# SAM_E54_Xplained_Pro_CAN.net
KiCad netlist of a schematic drawn in Altium Designer
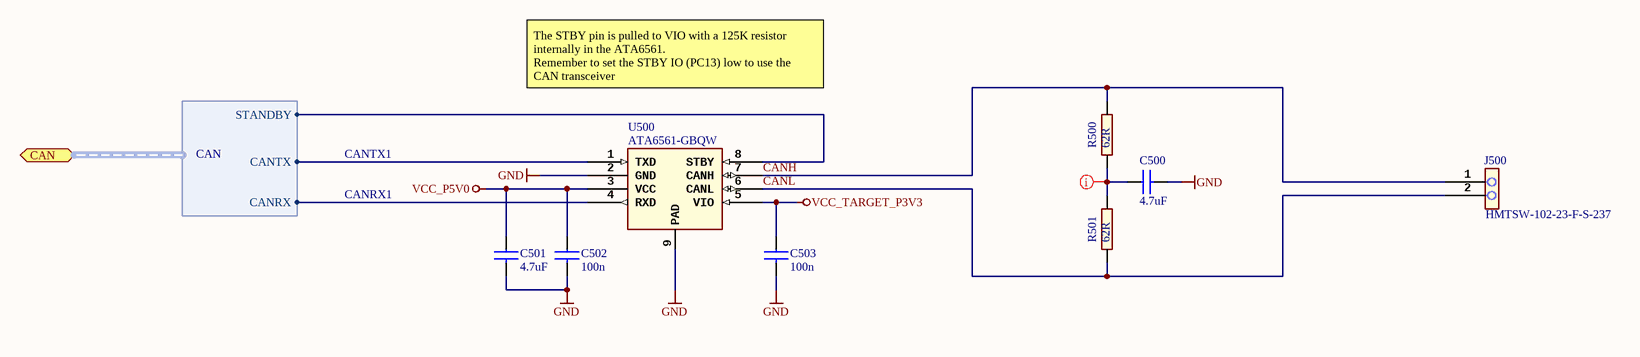
[diagram p0: SAM_E54_Xplained_Pro_CAN.SchDoc]

(export (version "E")
  (design (tool "Eeschema 10.0.6"))
  (components
    (comp (ref "C500")
      (value "4.7uF")
      (footprint "AP1-00003")
      (description "Ceramic capacitor, SMD 0805, X5R, 25V, Â±10 %")
      (fields (field (name "TOLERANCE") "Â±10%") (field (name "MANUFACTURER") "Murata"))
      (libsource (lib "AltiumDbLib") (part "CAP-NONPOL"))
    )
    (comp (ref "C501")
      (value "4.7uF")
      (footprint "AP1-00117")
      (description "Ceramic capacitor, SMD 0603, X5R, 10V, 10% (de31036)")
      (fields (field (name "TOLERANCE") "10%") (field (name "MANUFACTURER") "WALSIN Technology Corporation"))
      (libsource (lib "AltiumDbLib") (part "CAP-NONPOL"))
    )
    (comp (ref "C502")
      (value "100n")
      (footprint "AP1-00001")
      (description "Ceramic capacitor, SMD 0402, X7R, 16V, +/-10%")
      (fields (field (name "TOLERANCE") "16V, +/-10%") (field (name "MANUFACTURER") "Kemet"))
      (libsource (lib "AltiumDbLib") (part "CAP-NONPOL"))
    )
    (comp (ref "C503")
      (value "100n")
      (footprint "AP1-00001")
      (description "Ceramic capacitor, SMD 0402, X7R, 16V, +/-10%")
      (fields (field (name "TOLERANCE") "16V, +/-10%") (field (name "MANUFACTURER") "Kemet"))
      (libsource (lib "AltiumDbLib") (part "CAP-NONPOL"))
    )
    (comp (ref "J500")
      (value "HMTSW-102-23-F-S-237")
      (footprint "AP8-00733")
      (description "1x2 pin header, 2.54mm pitch, Pin-in-Paste THM")
      (fields (field (name "MANUFACTURER") "SAMTEC"))
      (libsource (lib "AltiumDbLib") (part "HEADER 1x2"))
    )
    (comp (ref "R500")
      (value "62R")
      (footprint "AP2-00008")
      (description "Thick film resistor, SMD 1210, 0.5W, 1%")
      (fields (field (name "TOLERANCE") "1%") (field (name "MANUFACTURER") "vishay"))
      (libsource (lib "AltiumDbLib") (part "R2"))
    )
    (comp (ref "R501")
      (value "62R")
      (footprint "AP2-00008")
      (description "Thick film resistor, SMD 1210, 0.5W, 1%")
      (fields (field (name "TOLERANCE") "1%") (field (name "MANUFACTURER") "vishay"))
      (libsource (lib "AltiumDbLib") (part "R2"))
    )
    (comp (ref "U500")
      (value "ATA6561-GBQW")
      (footprint "AP6-00407")
      (description "5Mbit/s CAN Trasceiver,VCC = 5V, VIO = 2.8-5V, 3x3 mm VDFN8")
      (fields (field (name "MANUFACTURER") "ATMEL"))
      (libsource (lib "AltiumDbLib") (part "ATA6561"))
    )
  )
  (nets
    (net (code "2") (name "/CANH") (class "Default")
      (node (ref "J500") (pin "1") (pinfunction "1_1") (pintype "passive"))
      (node (ref "R500") (pin "2") (pinfunction "2_2") (pintype "passive"))
      (node (ref "U500") (pin "7") (pinfunction "CANH_7") (pintype "bidirectional"))
    )
    (net (code "3") (name "/CANL") (class "Default")
      (node (ref "J500") (pin "2") (pinfunction "2_2") (pintype "passive"))
      (node (ref "R501") (pin "1") (pinfunction "1_1") (pintype "passive"))
      (node (ref "U500") (pin "6") (pinfunction "CANL_6") (pintype "bidirectional"))
    )
    (net (code "4") (name "/CANRX") (class "Default")
      (node (ref "U500") (pin "4") (pinfunction "RXD_4") (pintype "output"))
    )
    (net (code "5") (name "/CANTX") (class "Default")
      (node (ref "U500") (pin "1") (pinfunction "TXD_1") (pintype "input"))
    )
    (net (code "6") (name "/STANDBY") (class "Default")
      (node (ref "U500") (pin "8") (pinfunction "STBY_8") (pintype "input"))
    )
    (net (code "8") (name "GND") (class "Default")
      (node (ref "C500") (pin "2") (pinfunction "2_2") (pintype "passive"))
      (node (ref "C501") (pin "2") (pinfunction "2_2") (pintype "passive"))
      (node (ref "C502") (pin "2") (pinfunction "2_2") (pintype "passive"))
      (node (ref "C503") (pin "2") (pinfunction "2_2") (pintype "passive"))
      (node (ref "U500") (pin "2") (pinfunction "GND_2") (pintype "power_in"))
      (node (ref "U500") (pin "9") (pinfunction "PAD_9") (pintype "power_in"))
    )
    (net (code "9") (name "Net-(C500-Pad1)") (class "Default")
      (node (ref "C500") (pin "1") (pinfunction "1_1") (pintype "passive"))
      (node (ref "R500") (pin "1") (pinfunction "1_1") (pintype "passive"))
      (node (ref "R501") (pin "2") (pinfunction "2_2") (pintype "passive"))
    )
    (net (code "10") (name "VCC_P5V0") (class "Default")
      (node (ref "C501") (pin "1") (pinfunction "1_1") (pintype "passive"))
      (node (ref "C502") (pin "1") (pinfunction "1_1") (pintype "passive"))
      (node (ref "U500") (pin "3") (pinfunction "VCC_3") (pintype "power_in"))
    )
    (net (code "11") (name "VCC_TARGET_P3V3") (class "Default")
      (node (ref "C503") (pin "1") (pinfunction "1_1") (pintype "passive"))
      (node (ref "U500") (pin "5") (pinfunction "VIO_5") (pintype "input"))
    )
  )
)
